# Power.net
KiCad netlist of a schematic drawn in Altium Designer
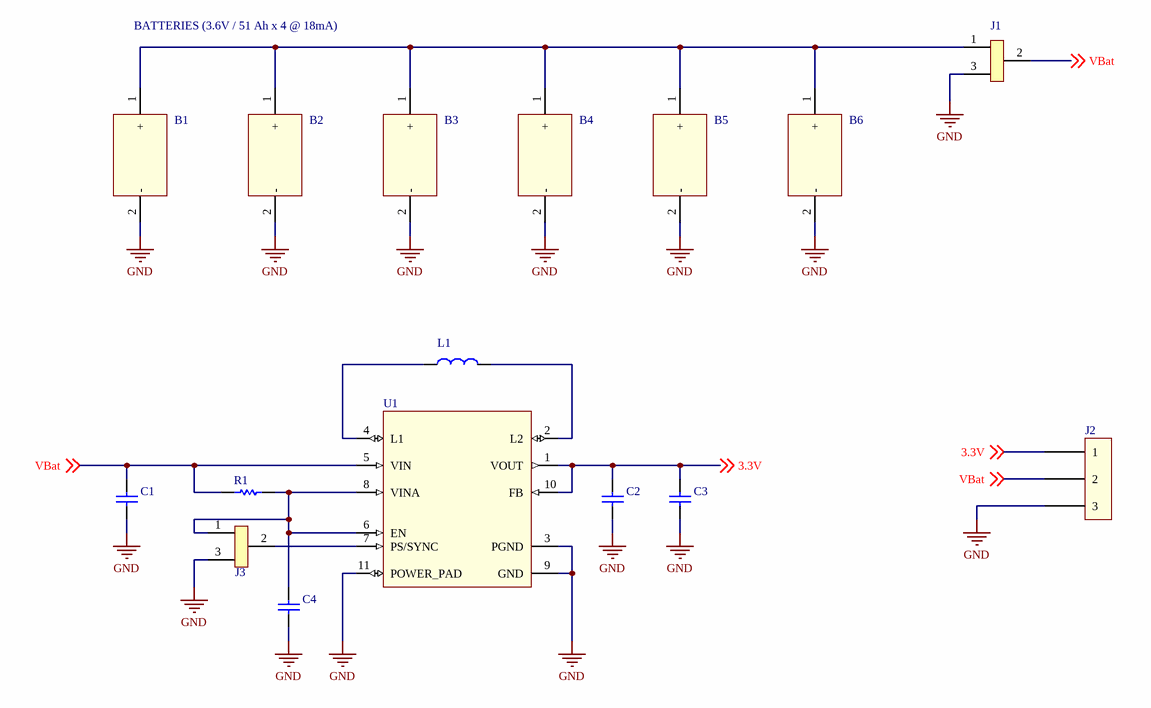
[diagram p0: Power.SchDoc]

(export (version "E")
  (design (tool "Eeschema 10.0.6"))
  (components
    (comp (ref "B1") (value "~") (footprint "KEYSTONE-2230") (libsource (lib "Keystone") (part "2230")))
    (comp (ref "B2") (value "~") (footprint "KEYSTONE-2230") (libsource (lib "Keystone") (part "2230")))
    (comp (ref "B3") (value "~") (footprint "KEYSTONE-2230") (libsource (lib "Keystone") (part "2230")))
    (comp (ref "B4") (value "~") (footprint "KEYSTONE-2230") (libsource (lib "Keystone") (part "2230")))
    (comp (ref "B5") (value "~") (footprint "KEYSTONE-2230") (libsource (lib "Keystone") (part "2230")))
    (comp (ref "B6") (value "~") (footprint "KEYSTONE-2230") (libsource (lib "Keystone") (part "2230")))
    (comp (ref "C1")
      (value "C0603C106M9PAC7867")
      (footprint "CAP-0603")
      (description "CAP CER 10uF 10V X5R 0603")
      (fields (field (name "MANUFACTURER") "Kemet") (field (name "TOLERANCE") "20%"))
      (libsource (lib "Kemet") (part "C0603C106M9PAC7867"))
    )
    (comp (ref "C2")
      (value "C0603C106M9PAC7867")
      (footprint "CAP-0603")
      (description "CAP CER 10uF 10V X5R 0603")
      (fields (field (name "MANUFACTURER") "Kemet") (field (name "TOLERANCE") "20%"))
      (libsource (lib "Kemet") (part "C0603C106M9PAC7867"))
    )
    (comp (ref "C3")
      (value "C0603C106M9PAC7867")
      (footprint "CAP-0603")
      (description "CAP CER 10uF 10V X5R 0603")
      (fields (field (name "MANUFACTURER") "Kemet") (field (name "TOLERANCE") "20%"))
      (libsource (lib "Kemet") (part "C0603C106M9PAC7867"))
    )
    (comp (ref "C4")
      (value "C0603C104K5RACAUTO")
      (footprint "CAP-0603")
      (description "CAP CER 0.1uF 50V X7R 0603")
      (fields (field (name "MANUFACTURER") "Kemet") (field (name "TOLERANCE") "10%"))
      (libsource (lib "Kemet") (part "C0603C104K5RACAUTO"))
    )
    (comp (ref "J1")
      (value "PRPC003SAAN-RC")
      (footprint "PIN3")
      (description "CONN HEADER .100\" SNGL STR 3POS")
      (fields (field (name "MANUFACTURER") "Sullins Connector Solutions"))
      (libsource (lib "Sullins") (part "PRPC003SAAN-RC"))
    )
    (comp (ref "J2")
      (value "~")
      (footprint "TE-640455-3")
      (description "CONN HEADER RTANG 3POS .100 TIN")
      (libsource (lib "TeConnectivity") (part "640455-3"))
    )
    (comp (ref "J3")
      (value "PRPC003SAAN-RC")
      (footprint "PIN3")
      (description "CONN HEADER .100\" SNGL STR 3POS")
      (fields (field (name "MANUFACTURER") "Sullins Connector Solutions"))
      (libsource (lib "Sullins") (part "PRPC003SAAN-RC"))
    )
    (comp (ref "L1")
      (value "LPS3015-222MRC")
      (footprint "COILCRAFT-LPS3015")
      (description "2.2 µH Shielded Inductor 1.4 A 110 mOhm")
      (fields (field (name "MANUFACTURER") "Coilcraft"))
      (libsource (lib "Coilcraft") (part "LPS3015-222MRC"))
    )
    (comp (ref "R1")
      (value "RC0805FR-07100KL")
      (footprint "RES-0603")
      (description "RES SMD 105 OHM 1% 1/8W 0805")
      (fields (field (name "TOLERANCE") "1%") (field (name "MANUFACTURER") "Yageo"))
      (libsource (lib "Yageo") (part "RC0805FR-07105RL"))
    )
    (comp (ref "U1")
      (value "~")
      (footprint "VSON10")
      (description "Buck Boost Regulator 3.3V 1.6A 10VSON")
      (fields (field (name "MANUFACTURER") "Texas Instruments"))
      (libsource (lib "TexasInstruments") (part "TPS63001DRCT"))
    )
  )
  (nets
    (net (code "1") (name "3.3V") (class "Default")
      (node (ref "C2") (pin "2") (pinfunction "2_2") (pintype "passive"))
      (node (ref "C3") (pin "2") (pinfunction "2_2") (pintype "passive"))
      (node (ref "J2") (pin "1") (pinfunction "1_1") (pintype "passive"))
      (node (ref "U1") (pin "1") (pinfunction "VOUT_1") (pintype "output"))
      (node (ref "U1") (pin "10") (pinfunction "FB_10") (pintype "input"))
    )
    (net (code "2") (name "GND") (class "Default")
      (node (ref "B1") (pin "2") (pinfunction "-_2") (pintype "passive"))
      (node (ref "B2") (pin "2") (pinfunction "-_2") (pintype "passive"))
      (node (ref "B3") (pin "2") (pinfunction "-_2") (pintype "passive"))
      (node (ref "B4") (pin "2") (pinfunction "-_2") (pintype "passive"))
      (node (ref "B5") (pin "2") (pinfunction "-_2") (pintype "passive"))
      (node (ref "B6") (pin "2") (pinfunction "-_2") (pintype "passive"))
      (node (ref "C1") (pin "1") (pinfunction "1_1") (pintype "passive"))
      (node (ref "C2") (pin "1") (pinfunction "1_1") (pintype "passive"))
      (node (ref "C3") (pin "1") (pinfunction "1_1") (pintype "passive"))
      (node (ref "C4") (pin "1") (pinfunction "1_1") (pintype "passive"))
      (node (ref "J1") (pin "3") (pinfunction "3_3") (pintype "passive"))
      (node (ref "J2") (pin "3") (pinfunction "3_3") (pintype "passive"))
      (node (ref "J3") (pin "3") (pinfunction "3_3") (pintype "passive"))
      (node (ref "U1") (pin "11") (pinfunction "POWER_PAD_11") (pintype "bidirectional"))
      (node (ref "U1") (pin "3") (pinfunction "PGND_3") (pintype "power_in"))
      (node (ref "U1") (pin "9") (pinfunction "GND_9") (pintype "power_in"))
    )
    (net (code "3") (name "Net-(B1-+)") (class "Default")
      (node (ref "B1") (pin "1") (pinfunction "+_1") (pintype "passive"))
      (node (ref "B2") (pin "1") (pinfunction "+_1") (pintype "passive"))
      (node (ref "B3") (pin "1") (pinfunction "+_1") (pintype "passive"))
      (node (ref "B4") (pin "1") (pinfunction "+_1") (pintype "passive"))
      (node (ref "B5") (pin "1") (pinfunction "+_1") (pintype "passive"))
      (node (ref "B6") (pin "1") (pinfunction "+_1") (pintype "passive"))
      (node (ref "J1") (pin "1") (pinfunction "1_1") (pintype "passive"))
    )
    (net (code "4") (name "Net-(U1-EN)") (class "Default")
      (node (ref "C4") (pin "2") (pinfunction "2_2") (pintype "passive"))
      (node (ref "J3") (pin "1") (pinfunction "1_1") (pintype "passive"))
      (node (ref "R1") (pin "2") (pinfunction "2_2") (pintype "passive"))
      (node (ref "U1") (pin "6") (pinfunction "EN_6") (pintype "input"))
      (node (ref "U1") (pin "8") (pinfunction "VINA_8") (pintype "input"))
    )
    (net (code "5") (name "Net-(U1-L1)") (class "Default")
      (node (ref "L1") (pin "1") (pinfunction "1_1") (pintype "passive"))
      (node (ref "U1") (pin "4") (pinfunction "L1_4") (pintype "bidirectional"))
    )
    (net (code "6") (name "Net-(U1-L2)") (class "Default")
      (node (ref "L1") (pin "2") (pinfunction "2_2") (pintype "passive"))
      (node (ref "U1") (pin "2") (pinfunction "L2_2") (pintype "bidirectional"))
    )
    (net (code "7") (name "Net-(U1-PS{slash}SYNC)") (class "Default")
      (node (ref "J3") (pin "2") (pinfunction "2_2") (pintype "passive"))
      (node (ref "U1") (pin "7") (pinfunction "PS/SYNC_7") (pintype "input"))
    )
    (net (code "8") (name "VBat") (class "Default")
      (node (ref "C1") (pin "2") (pinfunction "2_2") (pintype "passive"))
      (node (ref "J1") (pin "2") (pinfunction "2_2") (pintype "passive"))
      (node (ref "J2") (pin "2") (pinfunction "2_2") (pintype "passive"))
      (node (ref "R1") (pin "1") (pinfunction "1_1") (pintype "passive"))
      (node (ref "U1") (pin "5") (pinfunction "VIN_5") (pintype "input"))
    )
  )
)
